# 3_4.net
KiCad netlist of a schematic drawn in Altium Designer
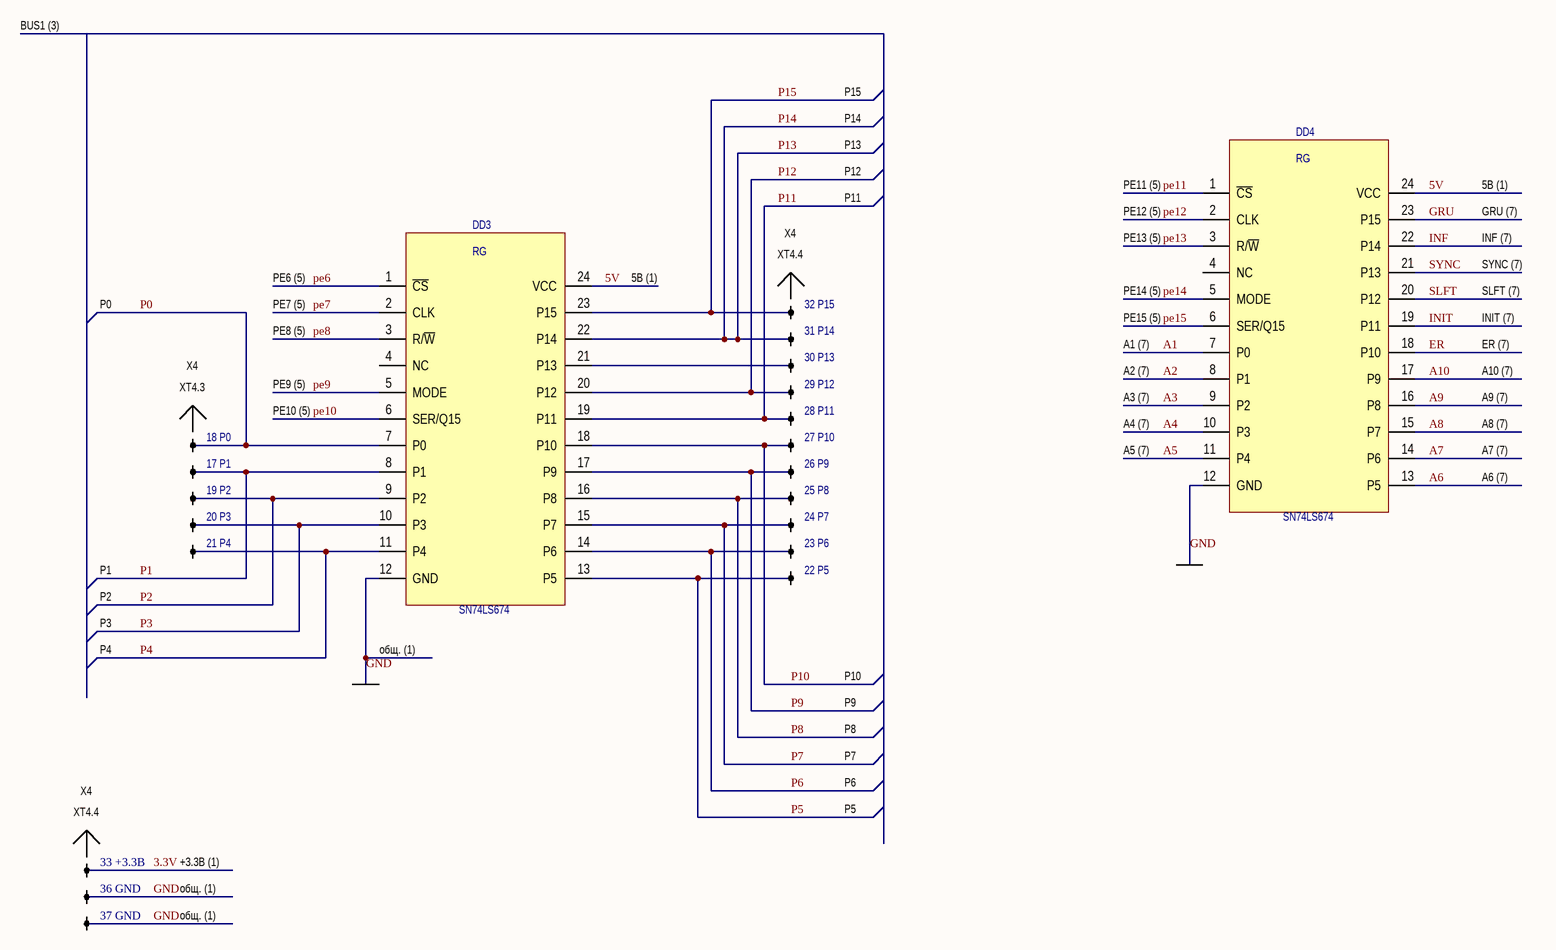
[diagram p0: Э3_4.SchDoc]

(export (version "E")
  (design (tool "Eeschema 10.0.6"))
  (components
    (comp (ref "DD3")
      (value "SN74LS674")
      (footprint "PcbLib1:SOP127P1030X265-24N")
      (libsource (lib "Schlib1") (part "SN74LS674"))
    )
    (comp (ref "DD4")
      (value "SN74LS674")
      (footprint "PcbLib1:SOP127P1030X265-24N")
      (libsource (lib "Schlib1") (part "SN74LS674"))
    )
    (comp (ref "X4") (value "17 P1") (footprint "PcbLib1:PLD40") (libsource (lib "") (part "PLD40_2")))
  )
  (nets
    (net (code "1") (name "/3.3V") (class "Default")
      (node (ref "X4") (pin "33") (pinfunction "1_33") (pintype "passive"))
    )
    (net (code "2") (name "/5V") (class "Default")
      (node (ref "DD3") (pin "24") (pinfunction "VCC_24") (pintype "passive"))
      (node (ref "DD4") (pin "24") (pinfunction "VCC_24") (pintype "passive"))
    )
    (net (code "3") (name "/A1") (class "Default")
      (node (ref "DD4") (pin "7") (pinfunction "P0_7") (pintype "passive"))
    )
    (net (code "4") (name "/A2") (class "Default")
      (node (ref "DD4") (pin "8") (pinfunction "P1_8") (pintype "passive"))
    )
    (net (code "5") (name "/A3") (class "Default")
      (node (ref "DD4") (pin "9") (pinfunction "P2_9") (pintype "passive"))
    )
    (net (code "6") (name "/A4") (class "Default")
      (node (ref "DD4") (pin "10") (pinfunction "P3_10") (pintype "passive"))
    )
    (net (code "7") (name "/A5") (class "Default")
      (node (ref "DD4") (pin "11") (pinfunction "P4_11") (pintype "passive"))
    )
    (net (code "8") (name "/A6") (class "Default")
      (node (ref "DD4") (pin "13") (pinfunction "P5_13") (pintype "passive"))
    )
    (net (code "9") (name "/A7") (class "Default")
      (node (ref "DD4") (pin "14") (pinfunction "P6_14") (pintype "passive"))
    )
    (net (code "10") (name "/A8") (class "Default")
      (node (ref "DD4") (pin "15") (pinfunction "P7_15") (pintype "passive"))
    )
    (net (code "11") (name "/A9") (class "Default")
      (node (ref "DD4") (pin "16") (pinfunction "P8_16") (pintype "passive"))
    )
    (net (code "12") (name "/A10") (class "Default")
      (node (ref "DD4") (pin "17") (pinfunction "P9_17") (pintype "passive"))
    )
    (net (code "13") (name "/ER") (class "Default")
      (node (ref "DD4") (pin "18") (pinfunction "P10_18") (pintype "passive"))
    )
    (net (code "14") (name "/GND") (class "Default")
      (node (ref "DD3") (pin "12") (pinfunction "GND_12") (pintype "passive"))
      (node (ref "DD4") (pin "12") (pinfunction "GND_12") (pintype "passive"))
      (node (ref "X4") (pin "36") (pinfunction "1_36") (pintype "passive"))
      (node (ref "X4") (pin "37") (pinfunction "1_37") (pintype "passive"))
    )
    (net (code "15") (name "/GRU") (class "Default")
      (node (ref "DD4") (pin "23") (pinfunction "P15_23") (pintype "passive"))
    )
    (net (code "16") (name "/INF") (class "Default")
      (node (ref "DD4") (pin "22") (pinfunction "P14_22") (pintype "passive"))
    )
    (net (code "17") (name "/INIT") (class "Default")
      (node (ref "DD4") (pin "19") (pinfunction "P11_19") (pintype "passive"))
    )
    (net (code "18") (name "/P0") (class "Default")
      (node (ref "DD3") (pin "7") (pinfunction "P0_7") (pintype "passive"))
      (node (ref "X4") (pin "32") (pinfunction "1_32") (pintype "passive"))
    )
    (net (code "19") (name "/P1") (class "Default")
      (node (ref "DD3") (pin "8") (pinfunction "P1_8") (pintype "passive"))
      (node (ref "X4") (pin "31") (pinfunction "1_31") (pintype "passive"))
    )
    (net (code "20") (name "/P2") (class "Default")
      (node (ref "DD3") (pin "9") (pinfunction "P2_9") (pintype "passive"))
      (node (ref "X4") (pin "33") (pinfunction "1_33") (pintype "passive"))
    )
    (net (code "21") (name "/P3") (class "Default")
      (node (ref "DD3") (pin "10") (pinfunction "P3_10") (pintype "passive"))
      (node (ref "X4") (pin "34") (pinfunction "1_34") (pintype "passive"))
    )
    (net (code "22") (name "/P4") (class "Default")
      (node (ref "DD3") (pin "11") (pinfunction "P4_11") (pintype "passive"))
      (node (ref "X4") (pin "35") (pinfunction "1_35") (pintype "passive"))
    )
    (net (code "23") (name "/P5") (class "Default")
      (node (ref "DD3") (pin "13") (pinfunction "P5_13") (pintype "passive"))
      (node (ref "X4") (pin "36") (pinfunction "1_36") (pintype "passive"))
    )
    (net (code "24") (name "/P6") (class "Default")
      (node (ref "DD3") (pin "14") (pinfunction "P6_14") (pintype "passive"))
      (node (ref "X4") (pin "37") (pinfunction "1_37") (pintype "passive"))
    )
    (net (code "25") (name "/P7") (class "Default")
      (node (ref "DD3") (pin "15") (pinfunction "P7_15") (pintype "passive"))
      (node (ref "X4") (pin "38") (pinfunction "1_38") (pintype "passive"))
    )
    (net (code "26") (name "/P8") (class "Default")
      (node (ref "DD3") (pin "16") (pinfunction "P8_16") (pintype "passive"))
      (node (ref "X4") (pin "39") (pinfunction "1_39") (pintype "passive"))
    )
    (net (code "27") (name "/P9") (class "Default")
      (node (ref "DD3") (pin "17") (pinfunction "P9_17") (pintype "passive"))
      (node (ref "X4") (pin "40") (pinfunction "1_40") (pintype "passive"))
    )
    (net (code "28") (name "/P10") (class "Default")
      (node (ref "DD3") (pin "18") (pinfunction "P10_18") (pintype "passive"))
      (node (ref "X4") (pin "2") (pinfunction "1_2") (pintype "passive"))
    )
    (net (code "29") (name "/P11") (class "Default")
      (node (ref "DD3") (pin "19") (pinfunction "P11_19") (pintype "passive"))
      (node (ref "X4") (pin "3") (pinfunction "1_3") (pintype "passive"))
    )
    (net (code "30") (name "/P12") (class "Default")
      (node (ref "DD3") (pin "20") (pinfunction "P12_20") (pintype "passive"))
      (node (ref "X4") (pin "4") (pinfunction "1_4") (pintype "passive"))
    )
    (net (code "31") (name "/P13") (class "Default")
      (node (ref "DD3") (pin "22") (pinfunction "P14_22") (pintype "passive"))
      (node (ref "X4") (pin "6") (pinfunction "1_6") (pintype "passive"))
    )
    (net (code "32") (name "/P15") (class "Default")
      (node (ref "DD3") (pin "23") (pinfunction "P15_23") (pintype "passive"))
      (node (ref "X4") (pin "7") (pinfunction "1_7") (pintype "passive"))
    )
    (net (code "33") (name "/SLFT") (class "Default")
      (node (ref "DD4") (pin "20") (pinfunction "P12_20") (pintype "passive"))
    )
    (net (code "34") (name "/SYNC") (class "Default")
      (node (ref "DD4") (pin "21") (pinfunction "P13_21") (pintype "passive"))
    )
    (net (code "35") (name "/pe6") (class "Default")
      (node (ref "DD3") (pin "1") (pinfunction "~{CS}_1") (pintype "passive"))
    )
    (net (code "36") (name "/pe7") (class "Default")
      (node (ref "DD3") (pin "2") (pinfunction "CLK_2") (pintype "passive"))
    )
    (net (code "37") (name "/pe8") (class "Default")
      (node (ref "DD3") (pin "3") (pinfunction "R/~{W}_3") (pintype "passive"))
    )
    (net (code "38") (name "/pe9") (class "Default")
      (node (ref "DD3") (pin "5") (pinfunction "MODE_5") (pintype "passive"))
    )
    (net (code "39") (name "/pe10") (class "Default")
      (node (ref "DD3") (pin "6") (pinfunction "SER/Q15_6") (pintype "passive"))
    )
    (net (code "40") (name "/pe11") (class "Default")
      (node (ref "DD4") (pin "1") (pinfunction "~{CS}_1") (pintype "passive"))
    )
    (net (code "41") (name "/pe12") (class "Default")
      (node (ref "DD4") (pin "2") (pinfunction "CLK_2") (pintype "passive"))
    )
    (net (code "42") (name "/pe13") (class "Default")
      (node (ref "DD4") (pin "3") (pinfunction "R/~{W}_3") (pintype "passive"))
    )
    (net (code "43") (name "/pe14") (class "Default")
      (node (ref "DD4") (pin "5") (pinfunction "MODE_5") (pintype "passive"))
    )
    (net (code "44") (name "/pe15") (class "Default")
      (node (ref "DD4") (pin "6") (pinfunction "SER/Q15_6") (pintype "passive"))
    )
    (net (code "45") (name "Net-(DD3-P13)") (class "Default")
      (node (ref "DD3") (pin "21") (pinfunction "P13_21") (pintype "passive"))
      (node (ref "X4") (pin "5") (pinfunction "1_5") (pintype "passive"))
    )
    (net (code "46") (name "unconnected-(DD3-NC-Pad4)") (class "Default")
      (node (ref "DD3") (pin "4") (pinfunction "NC_4") (pintype "passive"))
    )
    (net (code "47") (name "unconnected-(DD4-NC-Pad4)") (class "Default")
      (node (ref "DD4") (pin "4") (pinfunction "NC_4") (pintype "passive"))
    )
  )
)
